# AnalogueIO.net
KiCad netlist of a schematic drawn in Altium Designer
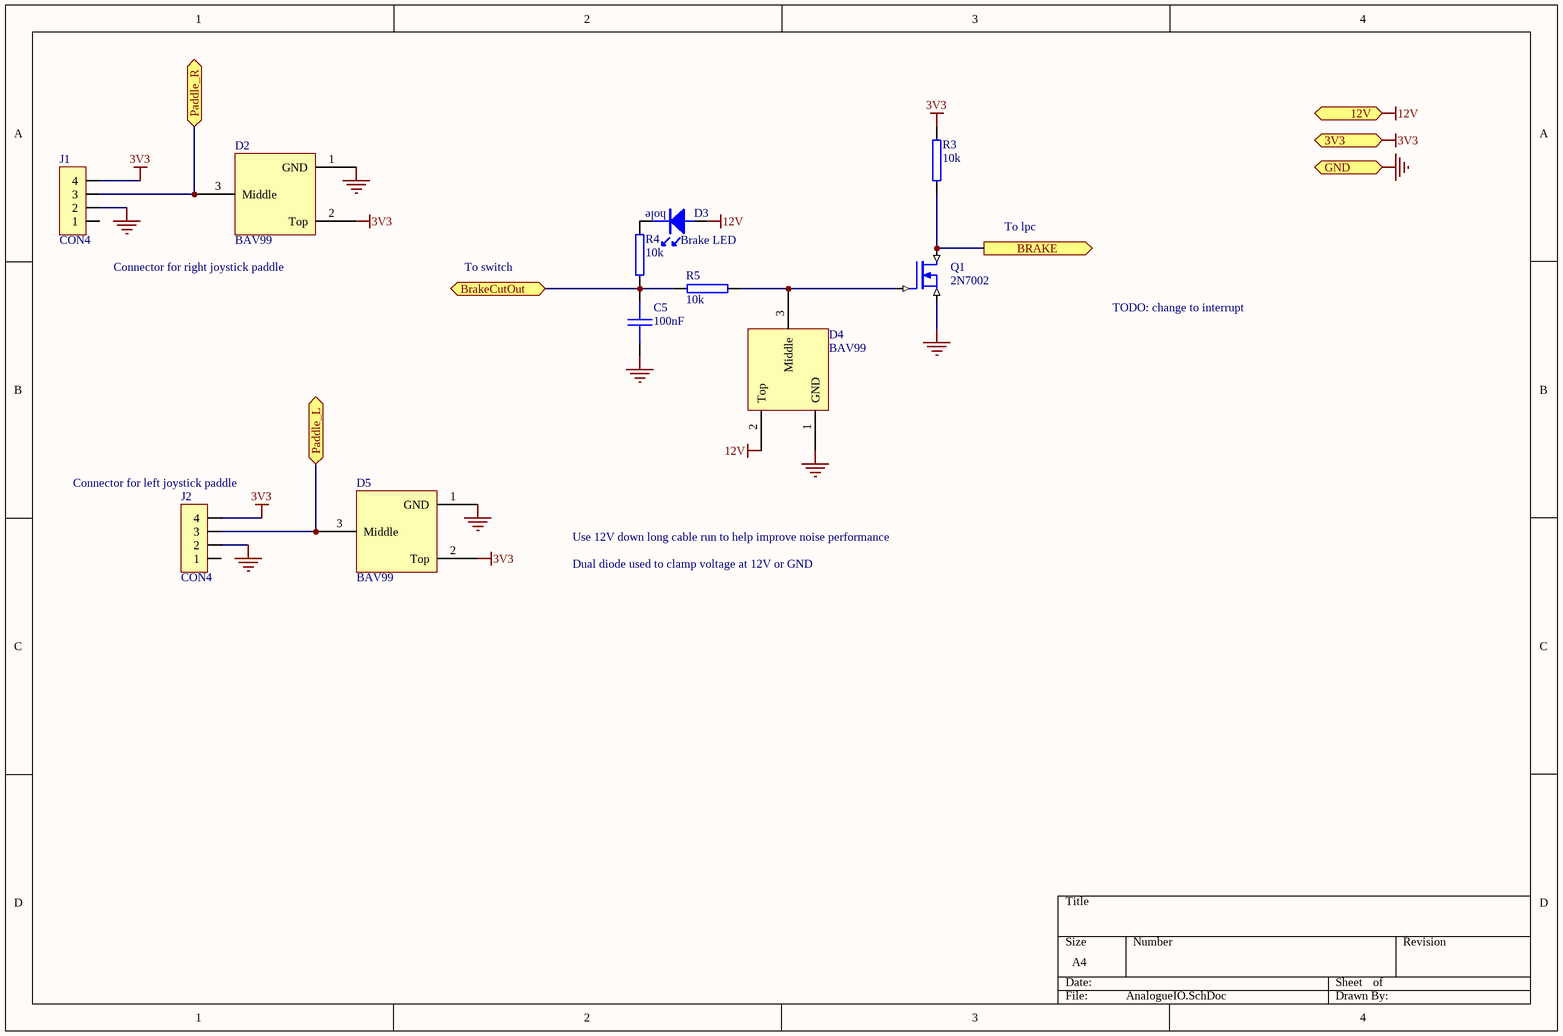
[diagram p0: AnalogueIO.SchDoc]

(export (version "E")
  (design (tool "Eeschema 10.0.6"))
  (components
    (comp (ref "C5")
      (value "100nF")
      (footprint "0603")
      (description "Capacitor")
      (libsource (lib "Miscellaneous Devices") (part "CAP"))
    )
    (comp (ref "D2")
      (value "BAV99")
      (footprint "dual  diode")
      (description "Dual Diode")
      (libsource (lib "Miscellaneous") (part "BAV99"))
    )
    (comp (ref "D3")
      (value "Brake LED")
      (footprint "3mm LED")
      (description "through hole LED")
      (libsource (lib "RCLDQ") (part "LED_HOLE"))
    )
    (comp (ref "D4")
      (value "BAV99")
      (footprint "dual  diode")
      (description "Dual Diode")
      (libsource (lib "") (part "BAV99_1"))
    )
    (comp (ref "D5")
      (value "BAV99")
      (footprint "dual  diode")
      (description "Dual Diode")
      (libsource (lib "Miscellaneous") (part "BAV99"))
    )
    (comp (ref "J1")
      (value "CON4")
      (footprint "MICROFIT-4-VERT")
      (description "Connector")
      (libsource (lib "Connectors") (part "CON4"))
    )
    (comp (ref "J2")
      (value "CON4")
      (footprint "MICROFIT-4-VERT")
      (description "Connector")
      (libsource (lib "Connectors") (part "CON4"))
    )
    (comp (ref "Q1") (value "2N7002") (footprint "SOT23-3") (libsource (lib "*") (part "N-MOSFET")))
    (comp (ref "R3")
      (value "10k")
      (footprint "0603")
      (description "Standard Resistor")
      (libsource (lib "*") (part "RES"))
    )
    (comp (ref "R4")
      (value "10k")
      (footprint "0603")
      (description "Standard Resistor")
      (libsource (lib "*") (part "RES"))
    )
    (comp (ref "R5")
      (value "10k")
      (footprint "0603")
      (description "Standard Resistor")
      (libsource (lib "*") (part "RES"))
    )
  )
  (nets
    (net (code "1") (name "/BRAKE") (class "Default")
      (node (ref "Q1") (pin "D") (pinfunction "D_D") (pintype "input"))
      (node (ref "R3") (pin "1") (pintype "passive"))
    )
    (net (code "2") (name "/BrakeCutOut") (class "Default")
      (node (ref "C5") (pin "1") (pinfunction "1_1") (pintype "passive"))
      (node (ref "R4") (pin "2") (pintype "passive"))
      (node (ref "R5") (pin "1") (pintype "passive"))
    )
    (net (code "3") (name "/Paddle_L") (class "Default")
      (node (ref "D5") (pin "3") (pinfunction "Middle_3") (pintype "passive"))
      (node (ref "J2") (pin "3") (pinfunction "3_3") (pintype "passive"))
    )
    (net (code "4") (name "/Paddle_R") (class "Default")
      (node (ref "D2") (pin "3") (pinfunction "Middle_3") (pintype "passive"))
      (node (ref "J1") (pin "3") (pinfunction "3_3") (pintype "passive"))
    )
    (net (code "5") (name "3V3") (class "Default")
      (node (ref "D2") (pin "2") (pinfunction "Top_2") (pintype "passive"))
      (node (ref "D5") (pin "2") (pinfunction "Top_2") (pintype "passive"))
      (node (ref "J1") (pin "4") (pinfunction "4_4") (pintype "passive"))
      (node (ref "J2") (pin "4") (pinfunction "4_4") (pintype "passive"))
      (node (ref "R3") (pin "2") (pintype "passive"))
    )
    (net (code "6") (name "12V") (class "Default")
      (node (ref "D3") (pin "A") (pinfunction "A_A") (pintype "passive"))
      (node (ref "D4") (pin "2") (pinfunction "Top_2") (pintype "passive"))
    )
    (net (code "7") (name "GND") (class "Default")
      (node (ref "C5") (pin "2") (pinfunction "2_2") (pintype "passive"))
      (node (ref "D2") (pin "1") (pinfunction "GND_1") (pintype "passive"))
      (node (ref "D4") (pin "1") (pinfunction "GND_1") (pintype "passive"))
      (node (ref "D5") (pin "1") (pinfunction "GND_1") (pintype "passive"))
      (node (ref "J1") (pin "2") (pinfunction "2_2") (pintype "passive"))
      (node (ref "J2") (pin "2") (pinfunction "2_2") (pintype "passive"))
      (node (ref "Q1") (pin "S") (pinfunction "S_S") (pintype "input"))
    )
    (net (code "8") (name "Net-(D3-PadK)") (class "Default")
      (node (ref "D3") (pin "K") (pinfunction "K_K") (pintype "passive"))
      (node (ref "R4") (pin "1") (pintype "passive"))
    )
    (net (code "9") (name "Net-(D4-Middle)") (class "Default")
      (node (ref "D4") (pin "3") (pinfunction "Middle_3") (pintype "passive"))
      (node (ref "Q1") (pin "G") (pinfunction "G_G") (pintype "input"))
      (node (ref "R5") (pin "2") (pintype "passive"))
    )
    (net (code "10") (name "unconnected-(J1-Pad1)") (class "Default")
      (node (ref "J1") (pin "1") (pinfunction "1_1") (pintype "passive"))
    )
    (net (code "11") (name "unconnected-(J2-Pad1)") (class "Default")
      (node (ref "J2") (pin "1") (pinfunction "1_1") (pintype "passive"))
    )
  )
)
